# zif_breakout_v10.net
KiCad netlist of a schematic drawn in EAGLE
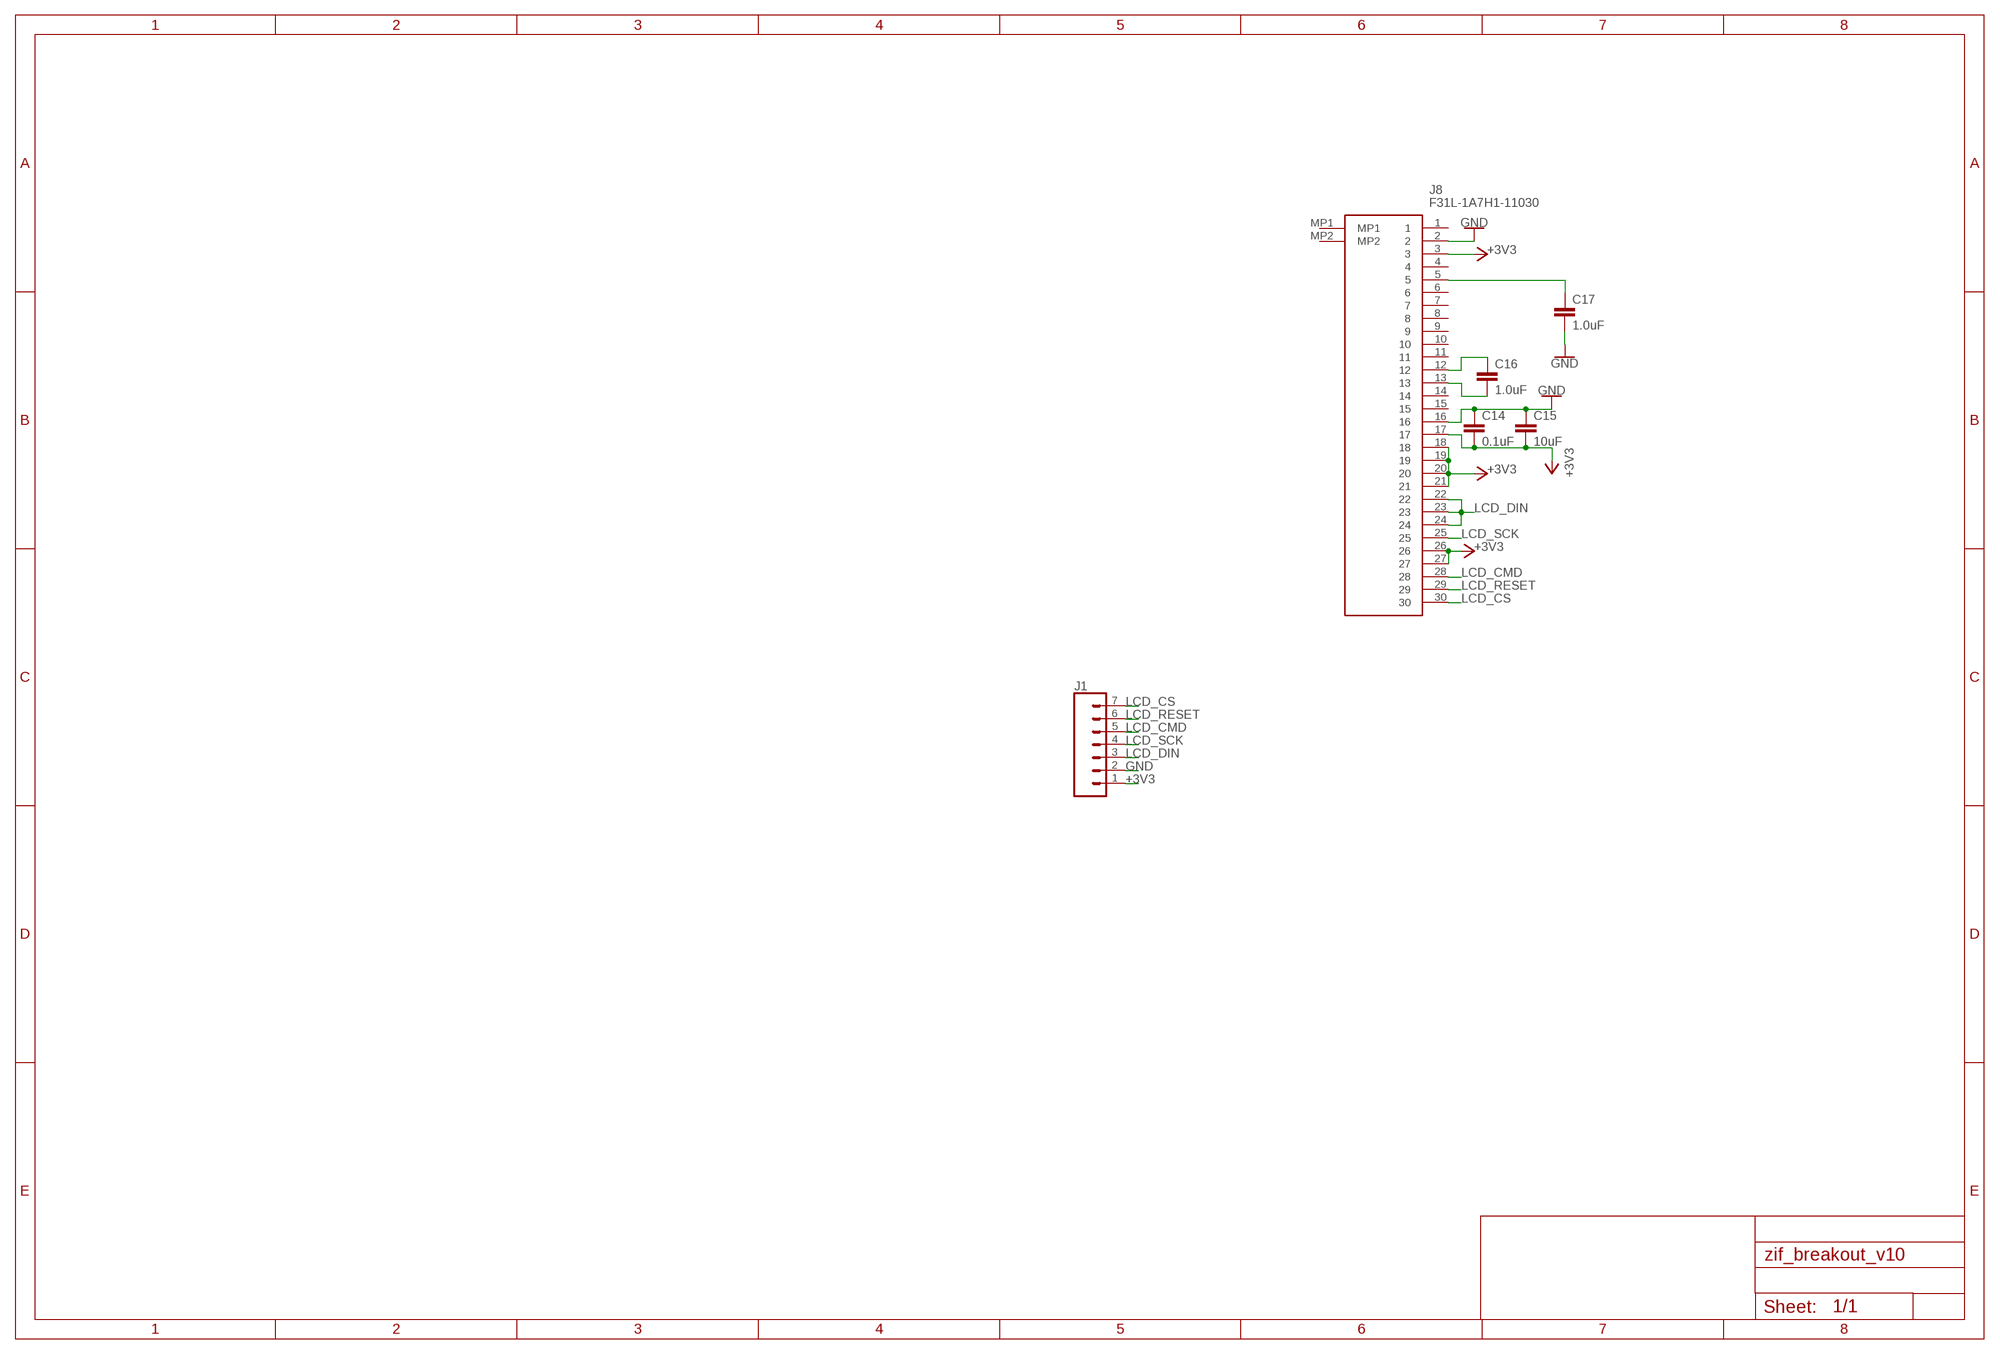
[diagram p0: schematic, sheet 1]

(export (version "E")
  (design (tool "Eeschema 10.0.6"))
  (components
    (comp (ref "C14")
      (value "0.1uF")
      (footprint "eagle-import:0603")
      (libsource (lib "eagle-import") (part "0.1UF-0603-25V-(+80/-20%)"))
    )
    (comp (ref "C15")
      (value "10uF")
      (footprint "eagle-import:0603")
      (libsource (lib "eagle-import") (part "10UF-0603-6.3V-20%"))
    )
    (comp (ref "C16")
      (value "1.0uF")
      (footprint "eagle-import:0603")
      (libsource (lib "eagle-import") (part "1.0UF-0603-16V-10%"))
    )
    (comp (ref "C17")
      (value "1.0uF")
      (footprint "eagle-import:0603")
      (libsource (lib "eagle-import") (part "1.0UF-0603-16V-10%"))
    )
    (comp (ref "J1")
      (value "CONN_07")
      (footprint "eagle-import:1X07")
      (libsource (lib "eagle-import") (part "CONN_07"))
    )
    (comp (ref "J8")
      (value "F31L-1A7H1-11030")
      (footprint "eagle-import:F31L1A7H111030")
      (fields (field (name "MOUSER_PART_NUMBER") "649-F31L-1A7H1-11030"))
      (libsource (lib "eagle-import") (part "F31L-1A7H1-11030"))
    )
  )
  (nets
    (net (code "1") (name "+3V3") (class "Default")
      (node (ref "C14") (pin "2") (pinfunction "2_2") (pintype "passive"))
      (node (ref "C15") (pin "2") (pinfunction "2_2") (pintype "passive"))
      (node (ref "J1") (pin "1") (pinfunction "1_1") (pintype "passive"))
      (node (ref "J8") (pin "17") (pinfunction "17_17") (pintype "bidirectional"))
      (node (ref "J8") (pin "18") (pinfunction "18_18") (pintype "bidirectional"))
      (node (ref "J8") (pin "19") (pinfunction "19_19") (pintype "bidirectional"))
      (node (ref "J8") (pin "20") (pinfunction "20_20") (pintype "bidirectional"))
      (node (ref "J8") (pin "21") (pinfunction "21_21") (pintype "bidirectional"))
      (node (ref "J8") (pin "26") (pinfunction "26_26") (pintype "bidirectional"))
      (node (ref "J8") (pin "27") (pinfunction "27_27") (pintype "bidirectional"))
      (node (ref "J8") (pin "3") (pinfunction "3_3") (pintype "bidirectional"))
    )
    (net (code "2") (name "/LCD_CMD") (class "Default")
      (node (ref "J1") (pin "5") (pinfunction "5_5") (pintype "passive"))
      (node (ref "J8") (pin "28") (pinfunction "28_28") (pintype "bidirectional"))
    )
    (net (code "3") (name "/LCD_CS") (class "Default")
      (node (ref "J1") (pin "7") (pinfunction "7_7") (pintype "passive"))
      (node (ref "J8") (pin "30") (pinfunction "30_30") (pintype "bidirectional"))
    )
    (net (code "4") (name "/LCD_DIN") (class "Default")
      (node (ref "J1") (pin "3") (pinfunction "3_3") (pintype "passive"))
      (node (ref "J8") (pin "22") (pinfunction "22_22") (pintype "bidirectional"))
      (node (ref "J8") (pin "23") (pinfunction "23_23") (pintype "bidirectional"))
      (node (ref "J8") (pin "24") (pinfunction "24_24") (pintype "bidirectional"))
    )
    (net (code "5") (name "/LCD_RESET") (class "Default")
      (node (ref "J1") (pin "6") (pinfunction "6_6") (pintype "passive"))
      (node (ref "J8") (pin "29") (pinfunction "29_29") (pintype "bidirectional"))
    )
    (net (code "6") (name "/LCD_SCK") (class "Default")
      (node (ref "J1") (pin "4") (pinfunction "4_4") (pintype "passive"))
      (node (ref "J8") (pin "25") (pinfunction "25_25") (pintype "bidirectional"))
    )
    (net (code "7") (name "GND") (class "Default")
      (node (ref "C14") (pin "1") (pinfunction "1_1") (pintype "passive"))
      (node (ref "C15") (pin "1") (pinfunction "1_1") (pintype "passive"))
      (node (ref "C17") (pin "2") (pinfunction "2_2") (pintype "passive"))
      (node (ref "J1") (pin "2") (pinfunction "2_2") (pintype "passive"))
      (node (ref "J8") (pin "16") (pinfunction "16_16") (pintype "bidirectional"))
      (node (ref "J8") (pin "2") (pinfunction "2_2") (pintype "bidirectional"))
    )
    (net (code "8") (name "Net-(C16-Pad1)") (class "Default")
      (node (ref "C16") (pin "1") (pinfunction "1_1") (pintype "passive"))
      (node (ref "J8") (pin "12") (pinfunction "12_12") (pintype "bidirectional"))
    )
    (net (code "9") (name "Net-(C16-Pad2)") (class "Default")
      (node (ref "C16") (pin "2") (pinfunction "2_2") (pintype "passive"))
      (node (ref "J8") (pin "13") (pinfunction "13_13") (pintype "bidirectional"))
    )
    (net (code "10") (name "Net-(C17-Pad1)") (class "Default")
      (node (ref "C17") (pin "1") (pinfunction "1_1") (pintype "passive"))
      (node (ref "J8") (pin "5") (pinfunction "5_5") (pintype "bidirectional"))
    )
    (net (code "11") (name "unconnected-(J8-Pad1)") (class "Default")
      (node (ref "J8") (pin "1") (pinfunction "1_1") (pintype "bidirectional"))
    )
    (net (code "12") (name "unconnected-(J8-Pad4)") (class "Default")
      (node (ref "J8") (pin "4") (pinfunction "4_4") (pintype "bidirectional"))
    )
    (net (code "13") (name "unconnected-(J8-Pad6)") (class "Default")
      (node (ref "J8") (pin "6") (pinfunction "6_6") (pintype "bidirectional"))
    )
    (net (code "14") (name "unconnected-(J8-Pad7)") (class "Default")
      (node (ref "J8") (pin "7") (pinfunction "7_7") (pintype "bidirectional"))
    )
    (net (code "15") (name "unconnected-(J8-Pad8)") (class "Default")
      (node (ref "J8") (pin "8") (pinfunction "8_8") (pintype "bidirectional"))
    )
    (net (code "16") (name "unconnected-(J8-Pad9)") (class "Default")
      (node (ref "J8") (pin "9") (pinfunction "9_9") (pintype "bidirectional"))
    )
    (net (code "17") (name "unconnected-(J8-Pad10)") (class "Default")
      (node (ref "J8") (pin "10") (pinfunction "10_10") (pintype "bidirectional"))
    )
    (net (code "18") (name "unconnected-(J8-Pad11)") (class "Default")
      (node (ref "J8") (pin "11") (pinfunction "11_11") (pintype "bidirectional"))
    )
    (net (code "19") (name "unconnected-(J8-Pad14)") (class "Default")
      (node (ref "J8") (pin "14") (pinfunction "14_14") (pintype "bidirectional"))
    )
    (net (code "20") (name "unconnected-(J8-Pad15)") (class "Default")
      (node (ref "J8") (pin "15") (pinfunction "15_15") (pintype "bidirectional"))
    )
    (net (code "21") (name "unconnected-(J8-PadMP1)") (class "Default")
      (node (ref "J8") (pin "MP1") (pinfunction "MP1_MP1") (pintype "bidirectional"))
    )
    (net (code "22") (name "unconnected-(J8-PadMP2)") (class "Default")
      (node (ref "J8") (pin "MP2") (pinfunction "MP2_MP2") (pintype "bidirectional"))
    )
  )
)
